# 2_MCU.net
KiCad netlist of a schematic drawn in Altium Designer
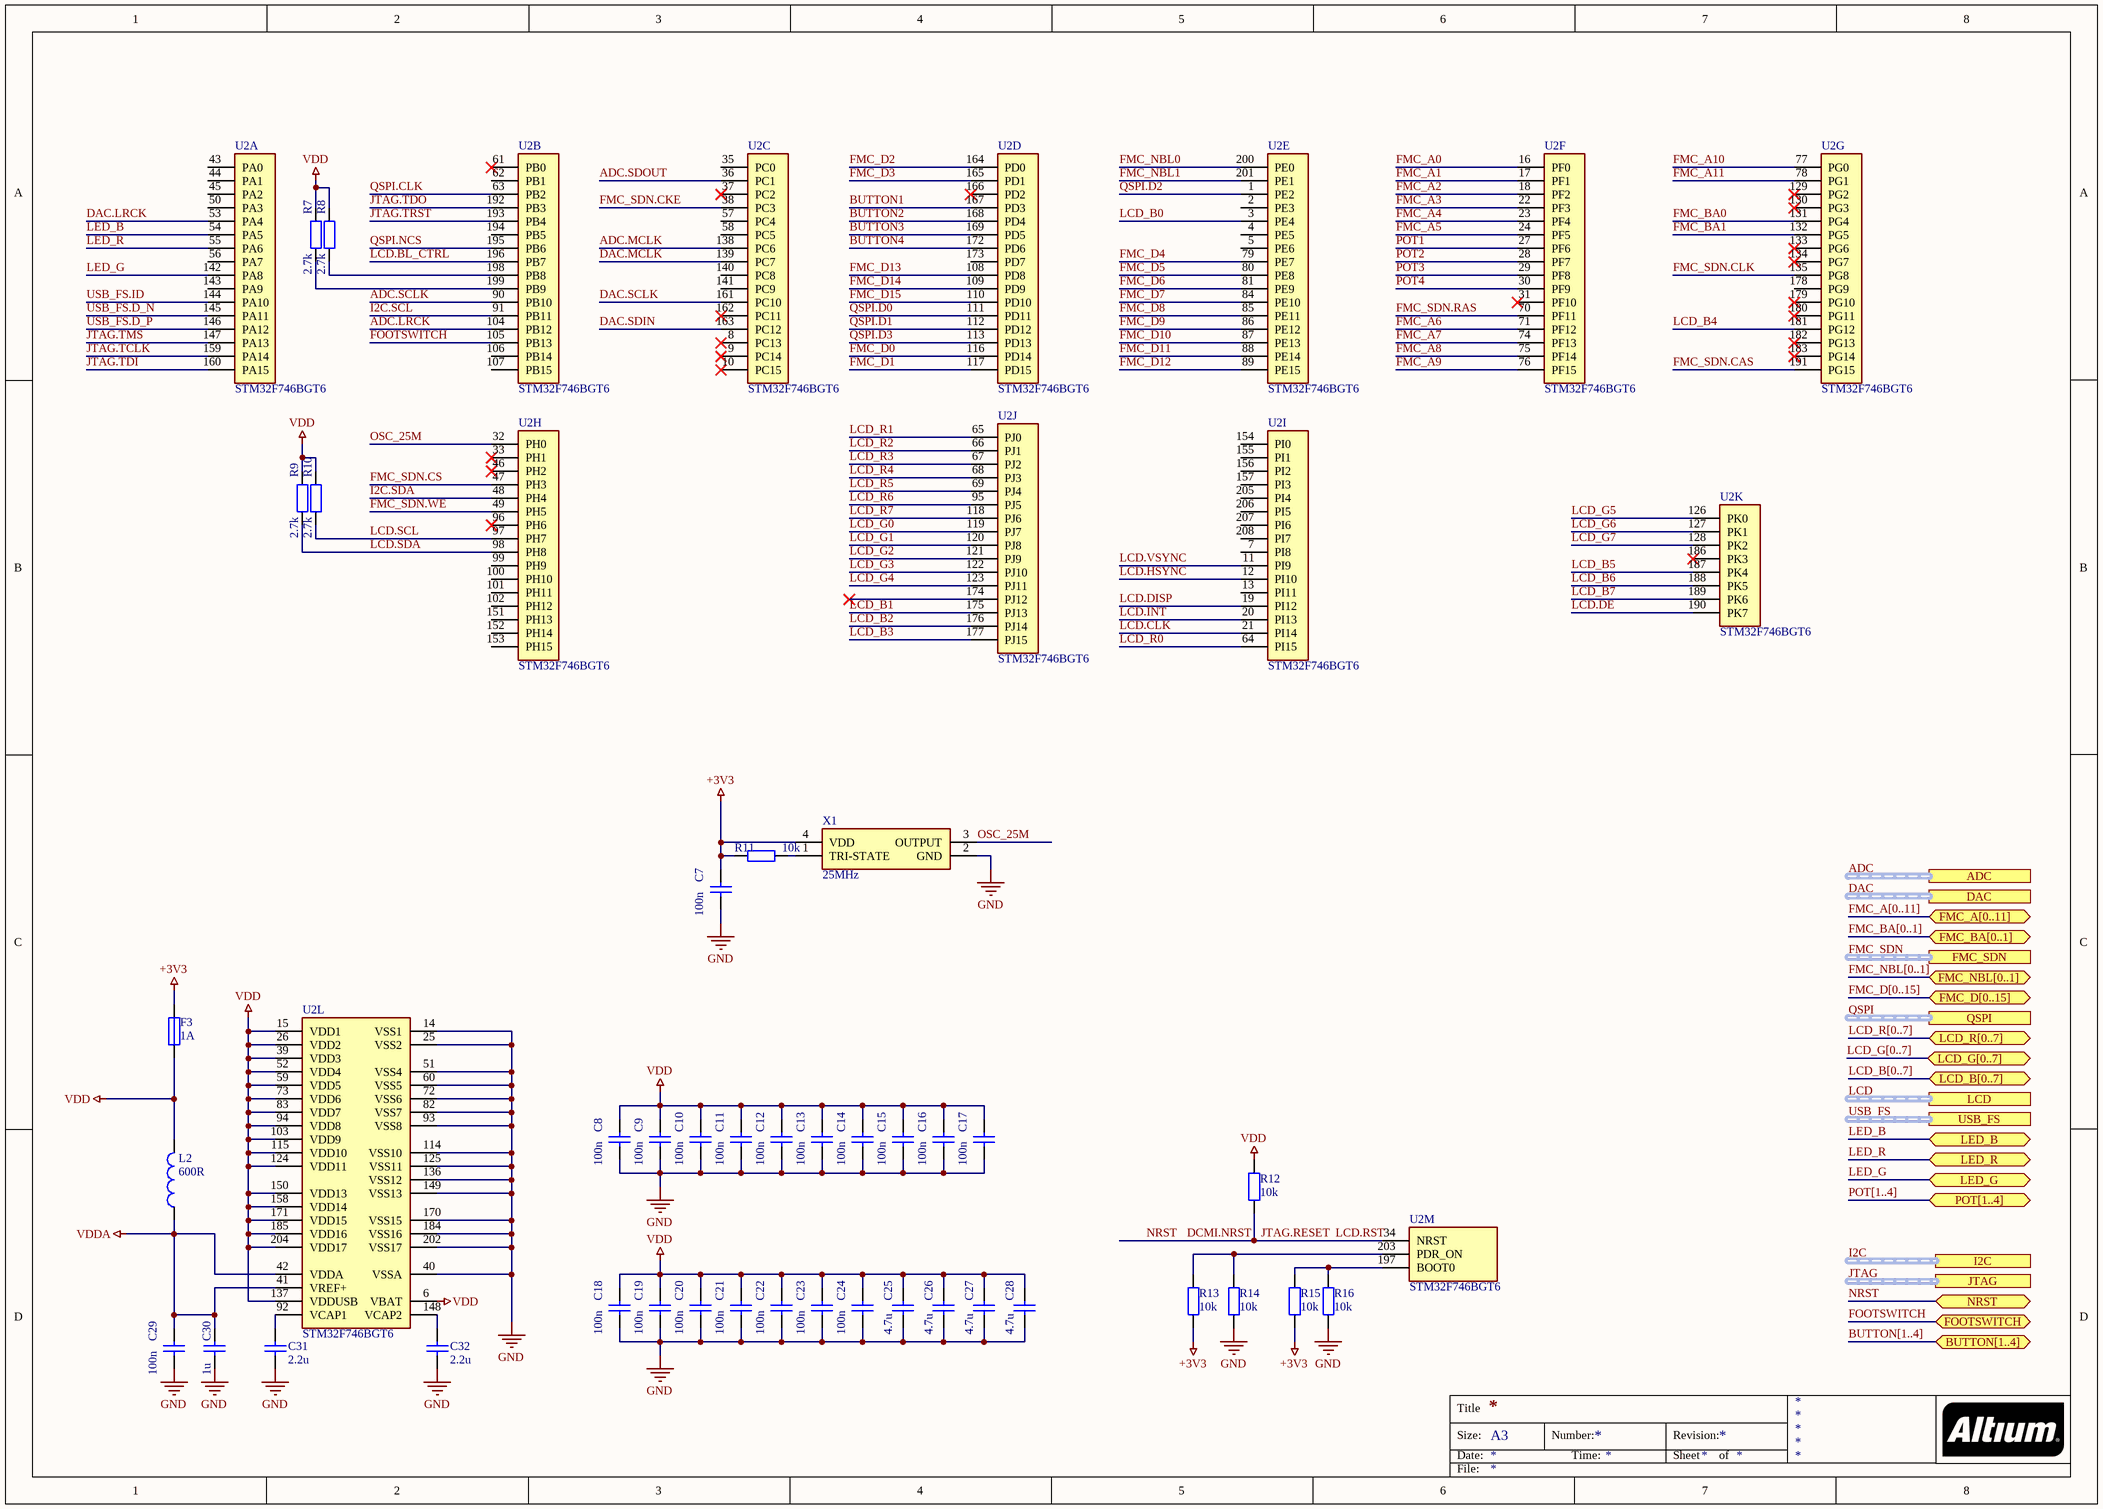
[diagram p0: [2] MCU.SchDoc]

(export (version "E")
  (design (tool "Eeschema 10.0.6"))
  (components
    (comp (ref "C7")
      (value "100n")
      (footprint "STguitar:Capacitor 0603")
      (description "Multilayer Ceramic Capacitors MLCC - SMD/SMT 0603 16VDC 0.1uF 10% X7R")
      (fields
        (field (name "MANUFACTURER PART NUMBER") "EMK107B7104KA-T")
        (field (name "MANUFACTURER") "Taiyo Yuden")
      )
      (libsource (lib "STguitar") (part "Capacitor 100n 10% 0603 EMK107B7104KA-T"))
    )
    (comp (ref "C8")
      (value "100n")
      (footprint "STguitar:Capacitor 0603")
      (description "Multilayer Ceramic Capacitors MLCC - SMD/SMT 0603 16VDC 0.1uF 10% X7R")
      (fields
        (field (name "MANUFACTURER PART NUMBER") "EMK107B7104KA-T")
        (field (name "MANUFACTURER") "Taiyo Yuden")
      )
      (libsource (lib "STguitar") (part "Capacitor 100n 10% 0603 EMK107B7104KA-T"))
    )
    (comp (ref "C9")
      (value "100n")
      (footprint "STguitar:Capacitor 0603")
      (description "Multilayer Ceramic Capacitors MLCC - SMD/SMT 0603 16VDC 0.1uF 10% X7R")
      (fields
        (field (name "MANUFACTURER PART NUMBER") "EMK107B7104KA-T")
        (field (name "MANUFACTURER") "Taiyo Yuden")
      )
      (libsource (lib "STguitar") (part "Capacitor 100n 10% 0603 EMK107B7104KA-T"))
    )
    (comp (ref "C10")
      (value "100n")
      (footprint "STguitar:Capacitor 0603")
      (description "Multilayer Ceramic Capacitors MLCC - SMD/SMT 0603 16VDC 0.1uF 10% X7R")
      (fields
        (field (name "MANUFACTURER PART NUMBER") "EMK107B7104KA-T")
        (field (name "MANUFACTURER") "Taiyo Yuden")
      )
      (libsource (lib "STguitar") (part "Capacitor 100n 10% 0603 EMK107B7104KA-T"))
    )
    (comp (ref "C11")
      (value "100n")
      (footprint "STguitar:Capacitor 0603")
      (description "Multilayer Ceramic Capacitors MLCC - SMD/SMT 0603 16VDC 0.1uF 10% X7R")
      (fields
        (field (name "MANUFACTURER PART NUMBER") "EMK107B7104KA-T")
        (field (name "MANUFACTURER") "Taiyo Yuden")
      )
      (libsource (lib "STguitar") (part "Capacitor 100n 10% 0603 EMK107B7104KA-T"))
    )
    (comp (ref "C12")
      (value "100n")
      (footprint "STguitar:Capacitor 0603")
      (description "Multilayer Ceramic Capacitors MLCC - SMD/SMT 0603 16VDC 0.1uF 10% X7R")
      (fields
        (field (name "MANUFACTURER PART NUMBER") "EMK107B7104KA-T")
        (field (name "MANUFACTURER") "Taiyo Yuden")
      )
      (libsource (lib "STguitar") (part "Capacitor 100n 10% 0603 EMK107B7104KA-T"))
    )
    (comp (ref "C13")
      (value "100n")
      (footprint "STguitar:Capacitor 0603")
      (description "Multilayer Ceramic Capacitors MLCC - SMD/SMT 0603 16VDC 0.1uF 10% X7R")
      (fields
        (field (name "MANUFACTURER PART NUMBER") "EMK107B7104KA-T")
        (field (name "MANUFACTURER") "Taiyo Yuden")
      )
      (libsource (lib "STguitar") (part "Capacitor 100n 10% 0603 EMK107B7104KA-T"))
    )
    (comp (ref "C14")
      (value "100n")
      (footprint "STguitar:Capacitor 0603")
      (description "Multilayer Ceramic Capacitors MLCC - SMD/SMT 0603 16VDC 0.1uF 10% X7R")
      (fields
        (field (name "MANUFACTURER PART NUMBER") "EMK107B7104KA-T")
        (field (name "MANUFACTURER") "Taiyo Yuden")
      )
      (libsource (lib "STguitar") (part "Capacitor 100n 10% 0603 EMK107B7104KA-T"))
    )
    (comp (ref "C15")
      (value "100n")
      (footprint "STguitar:Capacitor 0603")
      (description "Multilayer Ceramic Capacitors MLCC - SMD/SMT 0603 16VDC 0.1uF 10% X7R")
      (fields
        (field (name "MANUFACTURER PART NUMBER") "EMK107B7104KA-T")
        (field (name "MANUFACTURER") "Taiyo Yuden")
      )
      (libsource (lib "STguitar") (part "Capacitor 100n 10% 0603 EMK107B7104KA-T"))
    )
    (comp (ref "C16")
      (value "100n")
      (footprint "STguitar:Capacitor 0603")
      (description "Multilayer Ceramic Capacitors MLCC - SMD/SMT 0603 16VDC 0.1uF 10% X7R")
      (fields
        (field (name "MANUFACTURER PART NUMBER") "EMK107B7104KA-T")
        (field (name "MANUFACTURER") "Taiyo Yuden")
      )
      (libsource (lib "STguitar") (part "Capacitor 100n 10% 0603 EMK107B7104KA-T"))
    )
    (comp (ref "C17")
      (value "100n")
      (footprint "STguitar:Capacitor 0603")
      (description "Multilayer Ceramic Capacitors MLCC - SMD/SMT 0603 16VDC 0.1uF 10% X7R")
      (fields
        (field (name "MANUFACTURER PART NUMBER") "EMK107B7104KA-T")
        (field (name "MANUFACTURER") "Taiyo Yuden")
      )
      (libsource (lib "STguitar") (part "Capacitor 100n 10% 0603 EMK107B7104KA-T"))
    )
    (comp (ref "C18")
      (value "100n")
      (footprint "STguitar:Capacitor 0603")
      (description "Multilayer Ceramic Capacitors MLCC - SMD/SMT 0603 16VDC 0.1uF 10% X7R")
      (fields
        (field (name "MANUFACTURER PART NUMBER") "EMK107B7104KA-T")
        (field (name "MANUFACTURER") "Taiyo Yuden")
      )
      (libsource (lib "STguitar") (part "Capacitor 100n 10% 0603 EMK107B7104KA-T"))
    )
    (comp (ref "C19")
      (value "100n")
      (footprint "STguitar:Capacitor 0603")
      (description "Multilayer Ceramic Capacitors MLCC - SMD/SMT 0603 16VDC 0.1uF 10% X7R")
      (fields
        (field (name "MANUFACTURER PART NUMBER") "EMK107B7104KA-T")
        (field (name "MANUFACTURER") "Taiyo Yuden")
      )
      (libsource (lib "STguitar") (part "Capacitor 100n 10% 0603 EMK107B7104KA-T"))
    )
    (comp (ref "C20")
      (value "100n")
      (footprint "STguitar:Capacitor 0603")
      (description "Multilayer Ceramic Capacitors MLCC - SMD/SMT 0603 16VDC 0.1uF 10% X7R")
      (fields
        (field (name "MANUFACTURER PART NUMBER") "EMK107B7104KA-T")
        (field (name "MANUFACTURER") "Taiyo Yuden")
      )
      (libsource (lib "STguitar") (part "Capacitor 100n 10% 0603 EMK107B7104KA-T"))
    )
    (comp (ref "C21")
      (value "100n")
      (footprint "STguitar:Capacitor 0603")
      (description "Multilayer Ceramic Capacitors MLCC - SMD/SMT 0603 16VDC 0.1uF 10% X7R")
      (fields
        (field (name "MANUFACTURER PART NUMBER") "EMK107B7104KA-T")
        (field (name "MANUFACTURER") "Taiyo Yuden")
      )
      (libsource (lib "STguitar") (part "Capacitor 100n 10% 0603 EMK107B7104KA-T"))
    )
    (comp (ref "C22")
      (value "100n")
      (footprint "STguitar:Capacitor 0603")
      (description "Multilayer Ceramic Capacitors MLCC - SMD/SMT 0603 16VDC 0.1uF 10% X7R")
      (fields
        (field (name "MANUFACTURER PART NUMBER") "EMK107B7104KA-T")
        (field (name "MANUFACTURER") "Taiyo Yuden")
      )
      (libsource (lib "STguitar") (part "Capacitor 100n 10% 0603 EMK107B7104KA-T"))
    )
    (comp (ref "C23")
      (value "100n")
      (footprint "STguitar:Capacitor 0603")
      (description "Multilayer Ceramic Capacitors MLCC - SMD/SMT 0603 16VDC 0.1uF 10% X7R")
      (fields
        (field (name "MANUFACTURER PART NUMBER") "EMK107B7104KA-T")
        (field (name "MANUFACTURER") "Taiyo Yuden")
      )
      (libsource (lib "STguitar") (part "Capacitor 100n 10% 0603 EMK107B7104KA-T"))
    )
    (comp (ref "C24")
      (value "100n")
      (footprint "STguitar:Capacitor 0603")
      (description "Multilayer Ceramic Capacitors MLCC - SMD/SMT 0603 16VDC 0.1uF 10% X7R")
      (fields
        (field (name "MANUFACTURER PART NUMBER") "EMK107B7104KA-T")
        (field (name "MANUFACTURER") "Taiyo Yuden")
      )
      (libsource (lib "STguitar") (part "Capacitor 100n 10% 0603 EMK107B7104KA-T"))
    )
    (comp (ref "C25")
      (value "4.7u")
      (footprint "STguitar:Capacitor 0603")
      (description "Multilayer Ceramic Capacitors MLCC - SMD/SMT 0603 16VDC 4.7uF 10% X5R")
      (fields
        (field (name "MANUFACTURER PART NUMBER") "EMK107ABJ475KA-T")
        (field (name "MANUFACTURER") "Taiyo Yuden")
      )
      (libsource (lib "STguitar") (part "Capacitor 4.7u 10% 0603 EMK107ABJ475KA-T"))
    )
    (comp (ref "C26")
      (value "4.7u")
      (footprint "STguitar:Capacitor 0603")
      (description "Multilayer Ceramic Capacitors MLCC - SMD/SMT 0603 16VDC 4.7uF 10% X5R")
      (fields
        (field (name "MANUFACTURER PART NUMBER") "EMK107ABJ475KA-T")
        (field (name "MANUFACTURER") "Taiyo Yuden")
      )
      (libsource (lib "STguitar") (part "Capacitor 4.7u 10% 0603 EMK107ABJ475KA-T"))
    )
    (comp (ref "C27")
      (value "4.7u")
      (footprint "STguitar:Capacitor 0603")
      (description "Multilayer Ceramic Capacitors MLCC - SMD/SMT 0603 16VDC 4.7uF 10% X5R")
      (fields
        (field (name "MANUFACTURER PART NUMBER") "EMK107ABJ475KA-T")
        (field (name "MANUFACTURER") "Taiyo Yuden")
      )
      (libsource (lib "STguitar") (part "Capacitor 4.7u 10% 0603 EMK107ABJ475KA-T"))
    )
    (comp (ref "C28")
      (value "4.7u")
      (footprint "STguitar:Capacitor 0603")
      (description "Multilayer Ceramic Capacitors MLCC - SMD/SMT 0603 16VDC 4.7uF 10% X5R")
      (fields
        (field (name "MANUFACTURER PART NUMBER") "EMK107ABJ475KA-T")
        (field (name "MANUFACTURER") "Taiyo Yuden")
      )
      (libsource (lib "STguitar") (part "Capacitor 4.7u 10% 0603 EMK107ABJ475KA-T"))
    )
    (comp (ref "C29")
      (value "100n")
      (footprint "STguitar:Capacitor 0603")
      (description "Multilayer Ceramic Capacitors MLCC - SMD/SMT 0603 16VDC 0.1uF 10% X7R")
      (fields
        (field (name "MANUFACTURER PART NUMBER") "EMK107B7104KA-T")
        (field (name "MANUFACTURER") "Taiyo Yuden")
      )
      (libsource (lib "STguitar") (part "Capacitor 100n 10% 0603 EMK107B7104KA-T"))
    )
    (comp (ref "C30")
      (value "1u")
      (footprint "STguitar:Capacitor 0603")
      (description "Multilayer Ceramic Capacitors MLCC - SMD/SMT 0603 16VDC 1uF 10% X7R")
      (fields
        (field (name "MANUFACTURER PART NUMBER") "EMK107B7105KA-T")
        (field (name "MANUFACTURER") "Taiyo Yuden")
      )
      (libsource (lib "STguitar") (part "Capacitor 1u 10% 0603 EMK107B7105KA-T"))
    )
    (comp (ref "C31")
      (value "2.2u")
      (footprint "STguitar:Capacitor 0603")
      (description "Multilayer Ceramic Capacitors MLCC - SMD/SMT 0603 16VDC 2.2uF 10% X5R")
      (fields
        (field (name "MANUFACTURER PART NUMBER") "EMK107BJ225KA-T")
        (field (name "MANUFACTURER") "Taiyo Yuden")
      )
      (libsource (lib "STguitar") (part "Capacitor 2.2u 10% 0603 EMK107BJ225KA-T"))
    )
    (comp (ref "C32")
      (value "2.2u")
      (footprint "STguitar:Capacitor 0603")
      (description "Multilayer Ceramic Capacitors MLCC - SMD/SMT 0603 16VDC 2.2uF 10% X5R")
      (fields
        (field (name "MANUFACTURER PART NUMBER") "EMK107BJ225KA-T")
        (field (name "MANUFACTURER") "Taiyo Yuden")
      )
      (libsource (lib "STguitar") (part "Capacitor 2.2u 10% 0603 EMK107BJ225KA-T"))
    )
    (comp (ref "F3")
      (value "1A")
      (footprint "STguitar:Fuse 1206")
      (description "Surface Mount Fuses 1206 SMT Fuse Fast Acting, 1A")
      (fields (field (name "MANUFACTURER PART NUMBER") "C1F 1") (field (name "MANUFACTURER") "Bel Fuse"))
      (libsource (lib "STguitar") (part "Fuse 1206 SMT Fuse Fast Acting, 1A"))
    )
    (comp (ref "L2")
      (value "600R")
      (footprint "STguitar:Inductor 0603")
      (description "Ferrite Beads 600ohms 100MHz 300mA Monolithic 0603 SMD")
      (fields
        (field (name "MANUFACTURER PART NUMBER") "HZ0603C601R-10")
        (field (name "MANUFACTURER") "Laird Performance Materials")
      )
      (libsource (lib "STguitar") (part "Inductor 600R 1% 0603 HZ0603C601R-10"))
    )
    (comp (ref "R7")
      (value "2.7k")
      (footprint "STguitar:Resistor 0603")
      (description "Thin Film Resistors - SMD 1/10W 2.7K ohm 1% 50ppm")
      (fields
        (field (name "MANUFACTURER PART NUMBER") "RT0603FRE072K7L")
        (field (name "MANUFACTURER") "Yageo")
      )
      (libsource (lib "STguitar") (part "Resistor 2.7k 1% 0603 RT0603FRE072K7L"))
    )
    (comp (ref "R8")
      (value "2.7k")
      (footprint "STguitar:Resistor 0603")
      (description "Thin Film Resistors - SMD 1/10W 2.7K ohm 1% 50ppm")
      (fields
        (field (name "MANUFACTURER PART NUMBER") "RT0603FRE072K7L")
        (field (name "MANUFACTURER") "Yageo")
      )
      (libsource (lib "STguitar") (part "Resistor 2.7k 1% 0603 RT0603FRE072K7L"))
    )
    (comp (ref "R9")
      (value "2.7k")
      (footprint "STguitar:Resistor 0603")
      (description "Thin Film Resistors - SMD 1/10W 2.7K ohm 1% 50ppm")
      (fields
        (field (name "MANUFACTURER PART NUMBER") "RT0603FRE072K7L")
        (field (name "MANUFACTURER") "Yageo")
      )
      (libsource (lib "STguitar") (part "Resistor 2.7k 1% 0603 RT0603FRE072K7L"))
    )
    (comp (ref "R10")
      (value "2.7k")
      (footprint "STguitar:Resistor 0603")
      (description "Thin Film Resistors - SMD 1/10W 2.7K ohm 1% 50ppm")
      (fields
        (field (name "MANUFACTURER PART NUMBER") "RT0603FRE072K7L")
        (field (name "MANUFACTURER") "Yageo")
      )
      (libsource (lib "STguitar") (part "Resistor 2.7k 1% 0603 RT0603FRE072K7L"))
    )
    (comp (ref "R11")
      (value "10k")
      (footprint "STguitar:Resistor 0603")
      (description "Thin Film Resistors - SMD 10K ohm 1% 1/10W")
      (fields
        (field (name "MANUFACTURER PART NUMBER") "RT0603FRE0710KL")
        (field (name "MANUFACTURER") "Yageo")
      )
      (libsource (lib "") (part "Resistor 10k 1% 0603 RT0603FRE0710KL_1"))
    )
    (comp (ref "R12")
      (value "10k")
      (footprint "STguitar:Resistor 0603")
      (description "Thin Film Resistors - SMD 10K ohm 1% 1/10W")
      (fields
        (field (name "MANUFACTURER PART NUMBER") "RT0603FRE0710KL")
        (field (name "MANUFACTURER") "Yageo")
      )
      (libsource (lib "STguitar") (part "Resistor 10k 1% 0603 RT0603FRE0710KL"))
    )
    (comp (ref "R13")
      (value "10k")
      (footprint "STguitar:Resistor 0603")
      (description "Thin Film Resistors - SMD 10K ohm 1% 1/10W")
      (fields
        (field (name "MANUFACTURER PART NUMBER") "RT0603FRE0710KL")
        (field (name "MANUFACTURER") "Yageo")
      )
      (libsource (lib "STguitar") (part "Resistor 10k 1% 0603 RT0603FRE0710KL"))
    )
    (comp (ref "R14")
      (value "10k")
      (footprint "STguitar:Resistor 0603")
      (description "Thin Film Resistors - SMD 10K ohm 1% 1/10W")
      (fields
        (field (name "MANUFACTURER PART NUMBER") "RT0603FRE0710KL")
        (field (name "MANUFACTURER") "Yageo")
      )
      (libsource (lib "STguitar") (part "Resistor 10k 1% 0603 RT0603FRE0710KL"))
    )
    (comp (ref "R15")
      (value "10k")
      (footprint "STguitar:Resistor 0603")
      (description "Thin Film Resistors - SMD 10K ohm 1% 1/10W")
      (fields
        (field (name "MANUFACTURER PART NUMBER") "RT0603FRE0710KL")
        (field (name "MANUFACTURER") "Yageo")
      )
      (libsource (lib "STguitar") (part "Resistor 10k 1% 0603 RT0603FRE0710KL"))
    )
    (comp (ref "R16")
      (value "10k")
      (footprint "STguitar:Resistor 0603")
      (description "Thin Film Resistors - SMD 10K ohm 1% 1/10W")
      (fields
        (field (name "MANUFACTURER PART NUMBER") "RT0603FRE0710KL")
        (field (name "MANUFACTURER") "Yageo")
      )
      (libsource (lib "STguitar") (part "Resistor 10k 1% 0603 RT0603FRE0710KL"))
    )
    (comp (ref "U2")
      (value "STM32F746BGT6")
      (footprint "STguitar:TQFP208")
      (fields (field (name "MANUFACTURER") "STMicroelectronics"))
      (libsource (lib "STguitar") (part "IC MCU 32BIT 1MB FLASH 208LQFP STM32F746BGT6"))
    )
    (comp (ref "X1")
      (value "25MHz")
      (footprint "STguitar:Crystal 25MHz")
      (description "Standard Clock Oscillators Ultra-low Power MEMS Oscillator, 2520,-40C to+125C, 25ppm")
      (fields
        (field (name "MANUFACTURER PART NUMBER") "DSC6101JA2B-025.0000")
        (field (name "MANUFACTURER") "Microchip Technology")
      )
      (libsource (lib "STguitar") (part "Crystal 25MHz 2.5 mm x 2 mm DSC6101JA2B-025.0000"))
    )
  )
  (nets
    (net (code "9") (name "+3V3") (class "Default")
      (node (ref "C7") (pin "2") (pinfunction "2_2") (pintype "passive"))
      (node (ref "F3") (pin "2") (pinfunction "2_2") (pintype "passive"))
      (node (ref "R11") (pin "2") (pinfunction "2_2") (pintype "passive"))
      (node (ref "R13") (pin "1") (pinfunction "1_1") (pintype "passive"))
      (node (ref "R15") (pin "1") (pinfunction "1_1") (pintype "passive"))
      (node (ref "X1") (pin "4") (pinfunction "VDD_4") (pintype "passive"))
    )
    (net (code "10") (name "/ADC.LRCK") (class "Default")
      (node (ref "U2") (pin "104") (pinfunction "PB12_104") (pintype "passive"))
    )
    (net (code "11") (name "/ADC.MCLK") (class "Default")
      (node (ref "U2") (pin "138") (pinfunction "PC6_138") (pintype "passive"))
    )
    (net (code "12") (name "/ADC.SCLK") (class "Default")
      (node (ref "U2") (pin "90") (pinfunction "PB10_90") (pintype "passive"))
    )
    (net (code "13") (name "/ADC.SDOUT") (class "Default")
      (node (ref "U2") (pin "36") (pinfunction "PC1_36") (pintype "passive"))
    )
    (net (code "14") (name "/BUTTON1") (class "Default")
      (node (ref "U2") (pin "167") (pinfunction "PD3_167") (pintype "passive"))
    )
    (net (code "15") (name "/BUTTON2") (class "Default")
      (node (ref "U2") (pin "168") (pinfunction "PD4_168") (pintype "passive"))
    )
    (net (code "16") (name "/BUTTON3") (class "Default")
      (node (ref "U2") (pin "169") (pinfunction "PD5_169") (pintype "passive"))
    )
    (net (code "17") (name "/BUTTON4") (class "Default")
      (node (ref "U2") (pin "172") (pinfunction "PD6_172") (pintype "passive"))
    )
    (net (code "19") (name "/DAC.LRCK") (class "Default")
      (node (ref "U2") (pin "53") (pinfunction "PA4_53") (pintype "passive"))
    )
    (net (code "20") (name "/DAC.MCLK") (class "Default")
      (node (ref "U2") (pin "139") (pinfunction "PC7_139") (pintype "passive"))
    )
    (net (code "21") (name "/DAC.SCLK") (class "Default")
      (node (ref "U2") (pin "161") (pinfunction "PC10_161") (pintype "passive"))
    )
    (net (code "22") (name "/DAC.SDIN") (class "Default")
      (node (ref "U2") (pin "163") (pinfunction "PC12_163") (pintype "passive"))
    )
    (net (code "23") (name "/DCMI.NRST") (class "Default")
      (node (ref "R12") (pin "1") (pinfunction "1_1") (pintype "passive"))
      (node (ref "U2") (pin "34") (pinfunction "NRST_34") (pintype "passive"))
    )
    (net (code "24") (name "/FMC_A0") (class "Default")
      (node (ref "U2") (pin "16") (pinfunction "PF0_16") (pintype "passive"))
    )
    (net (code "25") (name "/FMC_A1") (class "Default")
      (node (ref "U2") (pin "17") (pinfunction "PF1_17") (pintype "passive"))
    )
    (net (code "26") (name "/FMC_A2") (class "Default")
      (node (ref "U2") (pin "18") (pinfunction "PF2_18") (pintype "passive"))
    )
    (net (code "27") (name "/FMC_A3") (class "Default")
      (node (ref "U2") (pin "22") (pinfunction "PF3_22") (pintype "passive"))
    )
    (net (code "28") (name "/FMC_A4") (class "Default")
      (node (ref "U2") (pin "23") (pinfunction "PF4_23") (pintype "passive"))
    )
    (net (code "29") (name "/FMC_A5") (class "Default")
      (node (ref "U2") (pin "24") (pinfunction "PF5_24") (pintype "passive"))
    )
    (net (code "30") (name "/FMC_A6") (class "Default")
      (node (ref "U2") (pin "71") (pinfunction "PF12_71") (pintype "passive"))
    )
    (net (code "31") (name "/FMC_A7") (class "Default")
      (node (ref "U2") (pin "74") (pinfunction "PF13_74") (pintype "passive"))
    )
    (net (code "32") (name "/FMC_A8") (class "Default")
      (node (ref "U2") (pin "75") (pinfunction "PF14_75") (pintype "passive"))
    )
    (net (code "33") (name "/FMC_A9") (class "Default")
      (node (ref "U2") (pin "76") (pinfunction "PF15_76") (pintype "passive"))
    )
    (net (code "34") (name "/FMC_A10") (class "Default")
      (node (ref "U2") (pin "77") (pinfunction "PG0_77") (pintype "passive"))
    )
    (net (code "35") (name "/FMC_A11") (class "Default")
      (node (ref "U2") (pin "78") (pinfunction "PG1_78") (pintype "passive"))
    )
    (net (code "37") (name "/FMC_BA0") (class "Default")
      (node (ref "U2") (pin "131") (pinfunction "PG4_131") (pintype "passive"))
    )
    (net (code "38") (name "/FMC_BA1") (class "Default")
      (node (ref "U2") (pin "132") (pinfunction "PG5_132") (pintype "passive"))
    )
    (net (code "40") (name "/FMC_D0") (class "Default")
      (node (ref "U2") (pin "116") (pinfunction "PD14_116") (pintype "passive"))
    )
    (net (code "41") (name "/FMC_D1") (class "Default")
      (node (ref "U2") (pin "117") (pinfunction "PD15_117") (pintype "passive"))
    )
    (net (code "42") (name "/FMC_D2") (class "Default")
      (node (ref "U2") (pin "164") (pinfunction "PD0_164") (pintype "passive"))
    )
    (net (code "43") (name "/FMC_D3") (class "Default")
      (node (ref "U2") (pin "165") (pinfunction "PD1_165") (pintype "passive"))
    )
    (net (code "44") (name "/FMC_D4") (class "Default")
      (node (ref "U2") (pin "79") (pinfunction "PE7_79") (pintype "passive"))
    )
    (net (code "45") (name "/FMC_D5") (class "Default")
      (node (ref "U2") (pin "80") (pinfunction "PE8_80") (pintype "passive"))
    )
    (net (code "46") (name "/FMC_D6") (class "Default")
      (node (ref "U2") (pin "81") (pinfunction "PE9_81") (pintype "passive"))
    )
    (net (code "47") (name "/FMC_D7") (class "Default")
      (node (ref "U2") (pin "84") (pinfunction "PE10_84") (pintype "passive"))
    )
    (net (code "48") (name "/FMC_D8") (class "Default")
      (node (ref "U2") (pin "85") (pinfunction "PE11_85") (pintype "passive"))
    )
    (net (code "49") (name "/FMC_D9") (class "Default")
      (node (ref "U2") (pin "86") (pinfunction "PE12_86") (pintype "passive"))
    )
    (net (code "50") (name "/FMC_D10") (class "Default")
      (node (ref "U2") (pin "87") (pinfunction "PE13_87") (pintype "passive"))
    )
    (net (code "51") (name "/FMC_D11") (class "Default")
      (node (ref "U2") (pin "88") (pinfunction "PE14_88") (pintype "passive"))
    )
    (net (code "52") (name "/FMC_D12") (class "Default")
      (node (ref "U2") (pin "89") (pinfunction "PE15_89") (pintype "passive"))
    )
    (net (code "53") (name "/FMC_D13") (class "Default")
      (node (ref "U2") (pin "108") (pinfunction "PD8_108") (pintype "passive"))
    )
    (net (code "54") (name "/FMC_D14") (class "Default")
      (node (ref "U2") (pin "109") (pinfunction "PD9_109") (pintype "passive"))
    )
    (net (code "55") (name "/FMC_D15") (class "Default")
      (node (ref "U2") (pin "110") (pinfunction "PD10_110") (pintype "passive"))
    )
    (net (code "57") (name "/FMC_NBL0") (class "Default")
      (node (ref "U2") (pin "200") (pinfunction "PE0_200") (pintype "passive"))
    )
    (net (code "58") (name "/FMC_NBL1") (class "Default")
      (node (ref "U2") (pin "201") (pinfunction "PE1_201") (pintype "passive"))
    )
    (net (code "60") (name "/FMC_SDN.CAS") (class "Default")
      (node (ref "U2") (pin "191") (pinfunction "PG15_191") (pintype "passive"))
    )
    (net (code "61") (name "/FMC_SDN.CKE") (class "Default")
      (node (ref "U2") (pin "38") (pinfunction "PC3_38") (pintype "passive"))
    )
    (net (code "62") (name "/FMC_SDN.CLK") (class "Default")
      (node (ref "U2") (pin "135") (pinfunction "PG8_135") (pintype "passive"))
    )
    (net (code "63") (name "/FMC_SDN.CS") (class "Default")
      (node (ref "U2") (pin "47") (pinfunction "PH3_47") (pintype "passive"))
    )
    (net (code "64") (name "/FMC_SDN.RAS") (class "Default")
      (node (ref "U2") (pin "70") (pinfunction "PF11_70") (pintype "passive"))
    )
    (net (code "65") (name "/FMC_SDN.WE") (class "Default")
      (node (ref "U2") (pin "49") (pinfunction "PH5_49") (pintype "passive"))
    )
    (net (code "66") (name "/FOOTSWITCH") (class "Default")
      (node (ref "U2") (pin "105") (pinfunction "PB13_105") (pintype "passive"))
    )
    (net (code "67") (name "/I2C.SCL") (class "Default")
      (node (ref "U2") (pin "91") (pinfunction "PB11_91") (pintype "passive"))
    )
    (net (code "68") (name "/I2C.SDA") (class "Default")
      (node (ref "U2") (pin "48") (pinfunction "PH4_48") (pintype "passive"))
    )
    (net (code "69") (name "/JTAG.TCLK") (class "Default")
      (node (ref "U2") (pin "159") (pinfunction "PA14_159") (pintype "passive"))
    )
    (net (code "70") (name "/JTAG.TDI") (class "Default")
      (node (ref "U2") (pin "160") (pinfunction "PA15_160") (pintype "passive"))
    )
    (net (code "71") (name "/JTAG.TDO") (class "Default")
      (node (ref "U2") (pin "192") (pinfunction "PB3_192") (pintype "passive"))
    )
    (net (code "72") (name "/JTAG.TMS") (class "Default")
      (node (ref "U2") (pin "147") (pinfunction "PA13_147") (pintype "passive"))
    )
    (net (code "73") (name "/JTAG.TRST") (class "Default")
      (node (ref "U2") (pin "193") (pinfunction "PB4_193") (pintype "passive"))
    )
    (net (code "74") (name "/LCD.BL_CTRL") (class "Default")
      (node (ref "U2") (pin "196") (pinfunction "PB7_196") (pintype "passive"))
    )
    (net (code "75") (name "/LCD.CLK") (class "Default")
      (node (ref "U2") (pin "21") (pinfunction "PI14_21") (pintype "passive"))
    )
    (net (code "76") (name "/LCD.DE") (class "Default")
      (node (ref "U2") (pin "190") (pinfunction "PK7_190") (pintype "passive"))
    )
    (net (code "77") (name "/LCD.DISP") (class "Default")
      (node (ref "U2") (pin "19") (pinfunction "PI12_19") (pintype "passive"))
    )
    (net (code "78") (name "/LCD.HSYNC") (class "Default")
      (node (ref "U2") (pin "12") (pinfunction "PI10_12") (pintype "passive"))
    )
    (net (code "79") (name "/LCD.INT") (class "Default")
      (node (ref "U2") (pin "20") (pinfunction "PI13_20") (pintype "passive"))
    )
    (net (code "80") (name "/LCD.SCL") (class "Default")
      (node (ref "R10") (pin "1") (pinfunction "1_1") (pintype "passive"))
      (node (ref "U2") (pin "97") (pinfunction "PH7_97") (pintype "passive"))
    )
    (net (code "81") (name "/LCD.SDA") (class "Default")
      (node (ref "R9") (pin "1") (pinfunction "1_1") (pintype "passive"))
      (node (ref "U2") (pin "98") (pinfunction "PH8_98") (pintype "passive"))
    )
    (net (code "82") (name "/LCD.VSYNC") (class "Default")
      (node (ref "U2") (pin "11") (pinfunction "PI9_11") (pintype "passive"))
    )
    (net (code "83") (name "/LCD_B0") (class "Default")
      (node (ref "U2") (pin "3") (pinfunction "PE4_3") (pintype "passive"))
    )
    (net (code "84") (name "/LCD_B1") (class "Default")
      (node (ref "U2") (pin "175") (pinfunction "PJ13_175") (pintype "passive"))
    )
    (net (code "85") (name "/LCD_B2") (class "Default")
      (node (ref "U2") (pin "176") (pinfunction "PJ14_176") (pintype "passive"))
    )
    (net (code "86") (name "/LCD_B3") (class "Default")
      (node (ref "U2") (pin "177") (pinfunction "PJ15_177") (pintype "passive"))
    )
    (net (code "87") (name "/LCD_B4") (class "Default")
      (node (ref "U2") (pin "181") (pinfunction "PG12_181") (pintype "passive"))
    )
    (net (code "88") (name "/LCD_B5") (class "Default")
      (node (ref "U2") (pin "187") (pinfunction "PK4_187") (pintype "passive"))
    )
    (net (code "89") (name "/LCD_B6") (class "Default")
      (node (ref "U2") (pin "188") (pinfunction "PK5_188") (pintype "passive"))
    )
    (net (code "90") (name "/LCD_B7") (class "Default")
      (node (ref "U2") (pin "189") (pinfunction "PK6_189") (pintype "passive"))
    )
    (net (code "92") (name "/LCD_G0") (class "Default")
      (node (ref "U2") (pin "119") (pinfunction "PJ7_119") (pintype "passive"))
    )
    (net (code "93") (name "/LCD_G1") (class "Default")
      (node (ref "U2") (pin "120") (pinfunction "PJ8_120") (pintype "passive"))
    )
    (net (code "94") (name "/LCD_G2") (class "Default")
      (node (ref "U2") (pin "121") (pinfunction "PJ9_121") (pintype "passive"))
    )
    (net (code "95") (name "/LCD_G3") (class "Default")
      (node (ref "U2") (pin "122") (pinfunction "PJ10_122") (pintype "passive"))
    )
    (net (code "96") (name "/LCD_G4") (class "Default")
      (node (ref "U2") (pin "123") (pinfunction "PJ11_123") (pintype "passive"))
    )
    (net (code "97") (name "/LCD_G5") (class "Default")
      (node (ref "U2") (pin "126") (pinfunction "PK0_126") (pintype "passive"))
    )
    (net (code "98") (name "/LCD_G6") (class "Default")
      (node (ref "U2") (pin "127") (pinfunction "PK1_127") (pintype "passive"))
    )
    (net (code "99") (name "/LCD_G7") (class "Default")
      (node (ref "U2") (pin "128") (pinfunction "PK2_128") (pintype "passive"))
    )
    (net (code "101") (name "/LCD_R0") (class "Default")
      (node (ref "U2") (pin "64") (pinfunction "PI15_64") (pintype "passive"))
    )
    (net (code "102") (name "/LCD_R1") (class "Default")
      (node (ref "U2") (pin "65") (pinfunction "PJ0_65") (pintype "passive"))
    )
    (net (code "103") (name "/LCD_R2") (class "Default")
      (node (ref "U2") (pin "66") (pinfunction "PJ1_66") (pintype "passive"))
    )
    (net (code "104") (name "/LCD_R3") (class "Default")
      (node (ref "U2") (pin "67") (pinfunction "PJ2_67") (pintype "passive"))
    )
    (net (code "105") (name "/LCD_R4") (class "Default")
      (node (ref "U2") (pin "68") (pinfunction "PJ3_68") (pintype "passive"))
    )
    (net (code "106") (name "/LCD_R5") (class "Default")
      (node (ref "U2") (pin "69") (pinfunction "PJ4_69") (pintype "passive"))
    )
    (net (code "107") (name "/LCD_R6") (class "Default")
      (node (ref "U2") (pin "95") (pinfunction "PJ5_95") (pintype "passive"))
    )
    (net (code "108") (name "/LCD_R7") (class "Default")
      (node (ref "U2") (pin "118") (pinfunction "PJ6_118") (pintype "passive"))
    )
    (net (code "110") (name "/LED_B") (class "Default")
      (node (ref "U2") (pin "54") (pinfunction "PA5_54") (pintype "passive"))
    )
    (net (code "111") (name "/LED_G") (class "Default")
      (node (ref "U2") (pin "142") (pinfunction "PA8_142") (pintype "passive"))
    )
    (net (code "112") (name "/LED_R") (class "Default")
      (node (ref "U2") (pin "55") (pinfunction "PA6_55") (pintype "passive"))
    )
    (net (code "113") (name "/OSC_25M") (class "Default")
      (node (ref "U2") (pin "32") (pinfunction "PH0_32") (pintype "passive"))
      (node (ref "X1") (pin "3") (pinfunction "OUTPUT_3") (pintype "passive"))
    )
    (net (code "114") (name "/POT1") (class "Default")
      (node (ref "U2") (pin "27") (pinfunction "PF6_27") (pintype "passive"))
    )
    (net (code "115") (name "/POT2") (class "Default")
      (node (ref "U2") (pin "28") (pinfunction "PF7_28") (pintype "passive"))
    )
    (net (code "116") (name "/POT3") (class "Default")
      (node (ref "U2") (pin "29") (pinfunction "PF8_29") (pintype "passive"))
    )
    (net (code "117") (name "/POT4") (class "Default")
      (node (ref "U2") (pin "30") (pinfunction "PF9_30") (pintype "passive"))
    )
    (net (code "119") (name "/QSPI.CLK") (class "Default")
      (node (ref "U2") (pin "63") (pinfunction "PB2_63") (pintype "passive"))
    )
    (net (code "120") (name "/QSPI.D0") (class "Default")
      (node (ref "U2") (pin "111") (pinfunction "PD11_111") (pintype "passive"))
    )
    (net (code "121") (name "/QSPI.D1") (class "Default")
      (node (ref "U2") (pin "112") (pinfunction "PD12_112") (pintype "passive"))
    )
    (net (code "122") (name "/QSPI.D2") (class "Default")
      (node (ref "U2") (pin "1") (pinfunction "PE2_1") (pintype "passive"))
    )
    (net (code "123") (name "/QSPI.D3") (class "Default")
      (node (ref "U2") (pin "113") (pinfunction "PD13_113") (pintype "passive"))
    )
    (net (code "124") (name "/QSPI.NCS") (class "Default")
      (node (ref "U2") (pin "195") (pinfunction "PB6_195") (pintype "passive"))
    )
    (net (code "125") (name "/USB_FS.D_N") (class "Default")
      (node (ref "U2") (pin "145") (pinfunction "PA11_145") (pintype "passive"))
    )
    (net (code "126") (name "/USB_FS.D_P") (class "Default")
      (node (ref "U2") (pin "146") (pinfunction "PA12_146") (pintype "passive"))
    )
    (net (code "127") (name "/USB_FS.ID") (class "Default")
      (node (ref "U2") (pin "144") (pinfunction "PA10_144") (pintype "passive"))
    )
    (net (code "136") (name "GND") (class "Default")
      (node (ref "C10") (pin "1") (pinfunction "1_1") (pintype "passive"))
      (node (ref "C11") (pin "1") (pinfunction "1_1") (pintype "passive"))
      (node (ref "C12") (pin "1") (pinfunction "1_1") (pintype "passive"))
      (node (ref "C13") (pin "1") (pinfunction "1_1") (pintype "passive"))
      (node (ref "C14") (pin "1") (pinfunction "1_1") (pintype "passive"))
      (node (ref "C15") (pin "1") (pinfunction "1_1") (pintype "passive"))
      (node (ref "C16") (pin "1") (pinfunction "1_1") (pintype "passive"))
      (node (ref "C17") (pin "1") (pinfunction "1_1") (pintype "passive"))
      (node (ref "C18") (pin "1") (pinfunction "1_1") (pintype "passive"))
      (node (ref "C19") (pin "1") (pinfunction "1_1") (pintype "passive"))
      (node (ref "C20") (pin "1") (pinfunction "1_1") (pintype "passive"))
      (node (ref "C21") (pin "1") (pinfunction "1_1") (pintype "passive"))
      (node (ref "C22") (pin "1") (pinfunction "1_1") (pintype "passive"))
      (node (ref "C23") (pin "1") (pinfunction "1_1") (pintype "passive"))
      (node (ref "C24") (pin "1") (pinfunction "1_1") (pintype "passive"))
      (node (ref "C25") (pin "1") (pinfunction "1_1") (pintype "passive"))
      (node (ref "C26") (pin "1") (pinfunction "1_1") (pintype "passive"))
      (node (ref "C27") (pin "1") (pinfunction "1_1") (pintype "passive"))
      (node (ref "C28") (pin "1") (pinfunction "1_1") (pintype "passive"))
      (node (ref "C29") (pin "1") (pinfunction "1_1") (pintype "passive"))
      (node (ref "C30") (pin "1") (pinfunction "1_1") (pintype "passive"))
      (node (ref "C31") (pin "1") (pinfunction "1_1") (pintype "passive"))
      (node (ref "C32") (pin "1") (pinfunction "1_1") (pintype "passive"))
      (node (ref "C7") (pin "1") (pinfunction "1_1") (pintype "passive"))
      (node (ref "C8") (pin "1") (pinfunction "1_1") (pintype "passive"))
      (node (ref "C9") (pin "1") (pinfunction "1_1") (pintype "passive"))
      (node (ref "R14") (pin "1") (pinfunction "1_1") (pintype "passive"))
      (node (ref "R16") (pin "1") (pinfunction "1_1") (pintype "passive"))
      (node (ref "U2") (pin "114") (pinfunction "VSS10_114") (pintype "passive"))
      (node (ref "U2") (pin "125") (pinfunction "VSS11_125") (pintype "passive"))
      (node (ref "U2") (pin "136") (pinfunction "VSS12_136") (pintype "passive"))
      (node (ref "U2") (pin "14") (pinfunction "VSS1_14") (pintype "passive"))
      (node (ref "U2") (pin "149") (pinfunction "VSS13_149") (pintype "passive"))
      (node (ref "U2") (pin "170") (pinfunction "VSS15_170") (pintype "passive"))
      (node (ref "U2") (pin "184") (pinfunction "VSS16_184") (pintype "passive"))
      (node (ref "U2") (pin "202") (pinfunction "VSS17_202") (pintype "passive"))
      (node (ref "U2") (pin "25") (pinfunction "VSS2_25") (pintype "passive"))
      (node (ref "U2") (pin "40") (pinfunction "VSSA_40") (pintype "passive"))
      (node (ref "U2") (pin "51") (pinfunction "VSS4_51") (pintype "passive"))
      (node (ref "U2") (pin "60") (pinfunction "VSS5_60") (pintype "passive"))
      (node (ref "U2") (pin "72") (pinfunction "VSS6_72") (pintype "passive"))
      (node (ref "U2") (pin "82") (pinfunction "VSS7_82") (pintype "passive"))
      (node (ref "U2") (pin "93") (pinfunction "VSS8_93") (pintype "passive"))
      (node (ref "X1") (pin "2") (pinfunction "GND_2") (pintype "passive"))
    )
    (net (code "137") (name "Net-(U2B-PB8)") (class "Default")
      (node (ref "R8") (pin "1") (pinfunction "1_1") (pintype "passive"))
      (node (ref "U2") (pin "198") (pinfunction "PB8_198") (pintype "passive"))
    )
    (net (code "138") (name "Net-(U2B-PB9)") (class "Default")
      (node (ref "R7") (pin "1") (pinfunction "1_1") (pintype "passive"))
      (node (ref "U2") (pin "199") (pinfunction "PB9_199") (pintype "passive"))
    )
    (net (code "139") (name "Net-(U2L-VCAP1)") (class "Default")
      (node (ref "C31") (pin "2") (pinfunction "2_2") (pintype "passive"))
      (node (ref "U2") (pin "92") (pinfunction "VCAP1_92") (pintype "passive"))
    )
    (net (code "140") (name "Net-(U2L-VCAP2)") (class "Default")
      (node (ref "C32") (pin "2") (pinfunction "2_2") (pintype "passive"))
      (node (ref "U2") (pin "148") (pinfunction "VCAP2_148") (pintype "passive"))
    )
    (net (code "141") (name "Net-(U2M-BOOT0)") (class "Default")
      (node (ref "R15") (pin "2") (pinfunction "2_2") (pintype "passive"))
      (node (ref "R16") (pin "2") (pinfunction "2_2") (pintype "passive"))
      (node (ref "U2") (pin "197") (pinfunction "BOOT0_197") (pintype "passive"))
    )
    (net (code "142") (name "Net-(U2M-PDR_ON)") (class "Default")
      (node (ref "R13") (pin "2") (pinfunction "2_2") (pintype "passive"))
      (node (ref "R14") (pin "2") (pinfunction "2_2") (pintype "passive"))
      (node (ref "U2") (pin "203") (pinfunction "PDR_ON_203") (pintype "passive"))
    )
    (net (code "143") (name "Net-(X1-TRI-STATE)") (class "Default")
      (node (ref "R11") (pin "1") (pinfunction "1_1") (pintype "passive"))
      (node (ref "X1") (pin "1") (pinfunction "TRI-STATE_1") (pintype "passive"))
    )
    (net (code "144") (name "VDD") (class "Default")
      (node (ref "C10") (pin "2") (pinfunction "2_2") (pintype "passive"))
      (node (ref "C11") (pin "2") (pinfunction "2_2") (pintype "passive"))
      (node (ref "C12") (pin "2") (pinfunction "2_2") (pintype "passive"))
      (node (ref "C13") (pin "2") (pinfunction "2_2") (pintype "passive"))
      (node (ref "C14") (pin "2") (pinfunction "2_2") (pintype "passive"))
      (node (ref "C15") (pin "2") (pinfunction "2_2") (pintype "passive"))
      (node (ref "C16") (pin "2") (pinfunction "2_2") (pintype "passive"))
      (node (ref "C17") (pin "2") (pinfunction "2_2") (pintype "passive"))
      (node (ref "C18") (pin "2") (pinfunction "2_2") (pintype "passive"))
      (node (ref "C19") (pin "2") (pinfunction "2_2") (pintype "passive"))
      (node (ref "C20") (pin "2") (pinfunction "2_2") (pintype "passive"))
      (node (ref "C21") (pin "2") (pinfunction "2_2") (pintype "passive"))
      (node (ref "C22") (pin "2") (pinfunction "2_2") (pintype "passive"))
      (node (ref "C23") (pin "2") (pinfunction "2_2") (pintype "passive"))
      (node (ref "C24") (pin "2") (pinfunction "2_2") (pintype "passive"))
      (node (ref "C25") (pin "2") (pinfunction "2_2") (pintype "passive"))
      (node (ref "C26") (pin "2") (pinfunction "2_2") (pintype "passive"))
      (node (ref "C27") (pin "2") (pinfunction "2_2") (pintype "passive"))
      (node (ref "C28") (pin "2") (pinfunction "2_2") (pintype "passive"))
      (node (ref "C8") (pin "2") (pinfunction "2_2") (pintype "passive"))
      (node (ref "C9") (pin "2") (pinfunction "2_2") (pintype "passive"))
      (node (ref "F3") (pin "1") (pinfunction "1_1") (pintype "passive"))
      (node (ref "L2") (pin "2") (pinfunction "2_2") (pintype "passive"))
      (node (ref "R10") (pin "2") (pinfunction "2_2") (pintype "passive"))
      (node (ref "R12") (pin "2") (pinfunction "2_2") (pintype "passive"))
      (node (ref "R7") (pin "2") (pinfunction "2_2") (pintype "passive"))
      (node (ref "R8") (pin "2") (pinfunction "2_2") (pintype "passive"))
      (node (ref "R9") (pin "2") (pinfunction "2_2") (pintype "passive"))
      (node (ref "U2") (pin "103") (pinfunction "VDD9_103") (pintype "passive"))
      (node (ref "U2") (pin "115") (pinfunction "VDD10_115") (pintype "passive"))
      (node (ref "U2") (pin "124") (pinfunction "VDD11_124") (pintype "passive"))
      (node (ref "U2") (pin "137") (pinfunction "VDDUSB_137") (pintype "passive"))
      (node (ref "U2") (pin "15") (pinfunction "VDD1_15") (pintype "passive"))
      (node (ref "U2") (pin "150") (pinfunction "VDD13_150") (pintype "passive"))
      (node (ref "U2") (pin "158") (pinfunction "VDD14_158") (pintype "passive"))
      (node (ref "U2") (pin "171") (pinfunction "VDD15_171") (pintype "passive"))
      (node (ref "U2") (pin "185") (pinfunction "VDD16_185") (pintype "passive"))
      (node (ref "U2") (pin "204") (pinfunction "VDD17_204") (pintype "passive"))
      (node (ref "U2") (pin "26") (pinfunction "VDD2_26") (pintype "passive"))
      (node (ref "U2") (pin "39") (pinfunction "VDD3_39") (pintype "passive"))
      (node (ref "U2") (pin "52") (pinfunction "VDD4_52") (pintype "passive"))
      (node (ref "U2") (pin "59") (pinfunction "VDD5_59") (pintype "passive"))
      (node (ref "U2") (pin "6") (pinfunction "VBAT_6") (pintype "passive"))
      (node (ref "U2") (pin "73") (pinfunction "VDD6_73") (pintype "passive"))
      (node (ref "U2") (pin "83") (pinfunction "VDD7_83") (pintype "passive"))
      (node (ref "U2") (pin "94") (pinfunction "VDD8_94") (pintype "passive"))
    )
    (net (code "145") (name "VDDA") (class "Default")
      (node (ref "C29") (pin "2") (pinfunction "2_2") (pintype "passive"))
      (node (ref "C30") (pin "2") (pinfunction "2_2") (pintype "passive"))
      (node (ref "L2") (pin "1") (pinfunction "1_1") (pintype "passive"))
      (node (ref "U2") (pin "41") (pinfunction "VREF+_41") (pintype "passive"))
      (node (ref "U2") (pin "42") (pinfunction "VDDA_42") (pintype "passive"))
    )
    (net (code "146") (name "unconnected-(U2A-PA0-Pad43)") (class "Default")
      (node (ref "U2") (pin "43") (pinfunction "PA0_43") (pintype "passive"))
    )
    (net (code "147") (name "unconnected-(U2A-PA1-Pad44)") (class "Default")
      (node (ref "U2") (pin "44") (pinfunction "PA1_44") (pintype "passive"))
    )
    (net (code "148") (name "unconnected-(U2A-PA2-Pad45)") (class "Default")
      (node (ref "U2") (pin "45") (pinfunction "PA2_45") (pintype "passive"))
    )
    (net (code "149") (name "unconnected-(U2A-PA3-Pad50)") (class "Default")
      (node (ref "U2") (pin "50") (pinfunction "PA3_50") (pintype "passive"))
    )
    (net (code "150") (name "unconnected-(U2A-PA7-Pad56)") (class "Default")
      (node (ref "U2") (pin "56") (pinfunction "PA7_56") (pintype "passive"))
    )
    (net (code "151") (name "unconnected-(U2A-PA9-Pad143)") (class "Default")
      (node (ref "U2") (pin "143") (pinfunction "PA9_143") (pintype "passive"))
    )
    (net (code "152") (name "unconnected-(U2B-PB0-Pad61)") (class "Default")
      (node (ref "U2") (pin "61") (pinfunction "PB0_61") (pintype "passive+no_connect"))
    )
    (net (code "153") (name "unconnected-(U2B-PB1-Pad62)") (class "Default")
      (node (ref "U2") (pin "62") (pinfunction "PB1_62") (pintype "passive"))
    )
    (net (code "154") (name "unconnected-(U2B-PB5-Pad194)") (class "Default")
      (node (ref "U2") (pin "194") (pinfunction "PB5_194") (pintype "passive"))
    )
    (net (code "155") (name "unconnected-(U2B-PB14-Pad106)") (class "Default")
      (node (ref "U2") (pin "106") (pinfunction "PB14_106") (pintype "passive"))
    )
    (net (code "156") (name "unconnected-(U2B-PB15-Pad107)") (class "Default")
      (node (ref "U2") (pin "107") (pinfunction "PB15_107") (pintype "passive"))
    )
    (net (code "157") (name "unconnected-(U2C-PC0-Pad35)") (class "Default")
      (node (ref "U2") (pin "35") (pinfunction "PC0_35") (pintype "passive"))
    )
    (net (code "158") (name "unconnected-(U2C-PC2-Pad37)") (class "Default")
      (node (ref "U2") (pin "37") (pinfunction "PC2_37") (pintype "passive+no_connect"))
    )
    (net (code "159") (name "unconnected-(U2C-PC4-Pad57)") (class "Default")
      (node (ref "U2") (pin "57") (pinfunction "PC4_57") (pintype "passive"))
    )
    (net (code "160") (name "unconnected-(U2C-PC5-Pad58)") (class "Default")
      (node (ref "U2") (pin "58") (pinfunction "PC5_58") (pintype "passive"))
    )
    (net (code "161") (name "unconnected-(U2C-PC8-Pad140)") (class "Default")
      (node (ref "U2") (pin "140") (pinfunction "PC8_140") (pintype "passive"))
    )
    (net (code "162") (name "unconnected-(U2C-PC9-Pad141)") (class "Default")
      (node (ref "U2") (pin "141") (pinfunction "PC9_141") (pintype "passive"))
    )
    (net (code "163") (name "unconnected-(U2C-PC11-Pad162)") (class "Default")
      (node (ref "U2") (pin "162") (pinfunction "PC11_162") (pintype "passive+no_connect"))
    )
    (net (code "164") (name "unconnected-(U2C-PC13-Pad8)") (class "Default")
      (node (ref "U2") (pin "8") (pinfunction "PC13_8") (pintype "passive+no_connect"))
    )
    (net (code "165") (name "unconnected-(U2C-PC14-Pad9)") (class "Default")
      (node (ref "U2") (pin "9") (pinfunction "PC14_9") (pintype "passive+no_connect"))
    )
    (net (code "166") (name "unconnected-(U2C-PC15-Pad10)") (class "Default")
      (node (ref "U2") (pin "10") (pinfunction "PC15_10") (pintype "passive+no_connect"))
    )
    (net (code "167") (name "unconnected-(U2D-PD2-Pad166)") (class "Default")
      (node (ref "U2") (pin "166") (pinfunction "PD2_166") (pintype "passive+no_connect"))
    )
    (net (code "168") (name "unconnected-(U2D-PD7-Pad173)") (class "Default")
      (node (ref "U2") (pin "173") (pinfunction "PD7_173") (pintype "passive"))
    )
    (net (code "169") (name "unconnected-(U2E-PE3-Pad2)") (class "Default")
      (node (ref "U2") (pin "2") (pinfunction "PE3_2") (pintype "passive"))
    )
    (net (code "170") (name "unconnected-(U2E-PE5-Pad4)") (class "Default")
      (node (ref "U2") (pin "4") (pinfunction "PE5_4") (pintype "passive"))
    )
    (net (code "171") (name "unconnected-(U2E-PE6-Pad5)") (class "Default")
      (node (ref "U2") (pin "5") (pinfunction "PE6_5") (pintype "passive"))
    )
    (net (code "172") (name "unconnected-(U2F-PF10-Pad31)") (class "Default")
      (node (ref "U2") (pin "31") (pinfunction "PF10_31") (pintype "passive+no_connect"))
    )
    (net (code "173") (name "unconnected-(U2G-PG2-Pad129)") (class "Default")
      (node (ref "U2") (pin "129") (pinfunction "PG2_129") (pintype "passive+no_connect"))
    )
    (net (code "174") (name "unconnected-(U2G-PG3-Pad130)") (class "Default")
      (node (ref "U2") (pin "130") (pinfunction "PG3_130") (pintype "passive+no_connect"))
    )
    (net (code "175") (name "unconnected-(U2G-PG6-Pad133)") (class "Default")
      (node (ref "U2") (pin "133") (pinfunction "PG6_133") (pintype "passive+no_connect"))
    )
    (net (code "176") (name "unconnected-(U2G-PG7-Pad134)") (class "Default")
      (node (ref "U2") (pin "134") (pinfunction "PG7_134") (pintype "passive+no_connect"))
    )
    (net (code "177") (name "unconnected-(U2G-PG9-Pad178)") (class "Default")
      (node (ref "U2") (pin "178") (pinfunction "PG9_178") (pintype "passive"))
    )
    (net (code "178") (name "unconnected-(U2G-PG10-Pad179)") (class "Default")
      (node (ref "U2") (pin "179") (pinfunction "PG10_179") (pintype "passive+no_connect"))
    )
    (net (code "179") (name "unconnected-(U2G-PG11-Pad180)") (class "Default")
      (node (ref "U2") (pin "180") (pinfunction "PG11_180") (pintype "passive+no_connect"))
    )
    (net (code "180") (name "unconnected-(U2G-PG13-Pad182)") (class "Default")
      (node (ref "U2") (pin "182") (pinfunction "PG13_182") (pintype "passive+no_connect"))
    )
    (net (code "181") (name "unconnected-(U2G-PG14-Pad183)") (class "Default")
      (node (ref "U2") (pin "183") (pinfunction "PG14_183") (pintype "passive+no_connect"))
    )
    (net (code "182") (name "unconnected-(U2H-PH1-Pad33)") (class "Default")
      (node (ref "U2") (pin "33") (pinfunction "PH1_33") (pintype "passive+no_connect"))
    )
    (net (code "183") (name "unconnected-(U2H-PH2-Pad46)") (class "Default")
      (node (ref "U2") (pin "46") (pinfunction "PH2_46") (pintype "passive+no_connect"))
    )
    (net (code "184") (name "unconnected-(U2H-PH6-Pad96)") (class "Default")
      (node (ref "U2") (pin "96") (pinfunction "PH6_96") (pintype "passive+no_connect"))
    )
    (net (code "185") (name "unconnected-(U2H-PH9-Pad99)") (class "Default")
      (node (ref "U2") (pin "99") (pinfunction "PH9_99") (pintype "passive"))
    )
    (net (code "186") (name "unconnected-(U2H-PH10-Pad100)") (class "Default")
      (node (ref "U2") (pin "100") (pinfunction "PH10_100") (pintype "passive"))
    )
    (net (code "187") (name "unconnected-(U2H-PH11-Pad101)") (class "Default")
      (node (ref "U2") (pin "101") (pinfunction "PH11_101") (pintype "passive"))
    )
    (net (code "188") (name "unconnected-(U2H-PH12-Pad102)") (class "Default")
      (node (ref "U2") (pin "102") (pinfunction "PH12_102") (pintype "passive"))
    )
    (net (code "189") (name "unconnected-(U2H-PH13-Pad151)") (class "Default")
      (node (ref "U2") (pin "151") (pinfunction "PH13_151") (pintype "passive"))
    )
    (net (code "190") (name "unconnected-(U2H-PH14-Pad152)") (class "Default")
      (node (ref "U2") (pin "152") (pinfunction "PH14_152") (pintype "passive"))
    )
    (net (code "191") (name "unconnected-(U2H-PH15-Pad153)") (class "Default")
      (node (ref "U2") (pin "153") (pinfunction "PH15_153") (pintype "passive"))
    )
    (net (code "192") (name "unconnected-(U2I-PI0-Pad154)") (class "Default")
      (node (ref "U2") (pin "154") (pinfunction "PI0_154") (pintype "passive"))
    )
    (net (code "193") (name "unconnected-(U2I-PI1-Pad155)") (class "Default")
      (node (ref "U2") (pin "155") (pinfunction "PI1_155") (pintype "passive"))
    )
    (net (code "194") (name "unconnected-(U2I-PI2-Pad156)") (class "Default")
      (node (ref "U2") (pin "156") (pinfunction "PI2_156") (pintype "passive"))
    )
    (net (code "195") (name "unconnected-(U2I-PI3-Pad157)") (class "Default")
      (node (ref "U2") (pin "157") (pinfunction "PI3_157") (pintype "passive"))
    )
    (net (code "196") (name "unconnected-(U2I-PI4-Pad205)") (class "Default")
      (node (ref "U2") (pin "205") (pinfunction "PI4_205") (pintype "passive"))
    )
    (net (code "197") (name "unconnected-(U2I-PI5-Pad206)") (class "Default")
      (node (ref "U2") (pin "206") (pinfunction "PI5_206") (pintype "passive"))
    )
    (net (code "198") (name "unconnected-(U2I-PI6-Pad207)") (class "Default")
      (node (ref "U2") (pin "207") (pinfunction "PI6_207") (pintype "passive"))
    )
    (net (code "199") (name "unconnected-(U2I-PI7-Pad208)") (class "Default")
      (node (ref "U2") (pin "208") (pinfunction "PI7_208") (pintype "passive"))
    )
    (net (code "200") (name "unconnected-(U2I-PI8-Pad7)") (class "Default")
      (node (ref "U2") (pin "7") (pinfunction "PI8_7") (pintype "passive"))
    )
    (net (code "201") (name "unconnected-(U2I-PI11-Pad13)") (class "Default")
      (node (ref "U2") (pin "13") (pinfunction "PI11_13") (pintype "passive"))
    )
    (net (code "202") (name "unconnected-(U2J-PJ12-Pad174)") (class "Default")
      (node (ref "U2") (pin "174") (pinfunction "PJ12_174") (pintype "passive+no_connect"))
    )
    (net (code "203") (name "unconnected-(U2K-PK3-Pad186)") (class "Default")
      (node (ref "U2") (pin "186") (pinfunction "PK3_186") (pintype "passive+no_connect"))
    )
  )
)
